# MAPLE-IR-V01.net
KiCad netlist of a schematic drawn in EAGLE
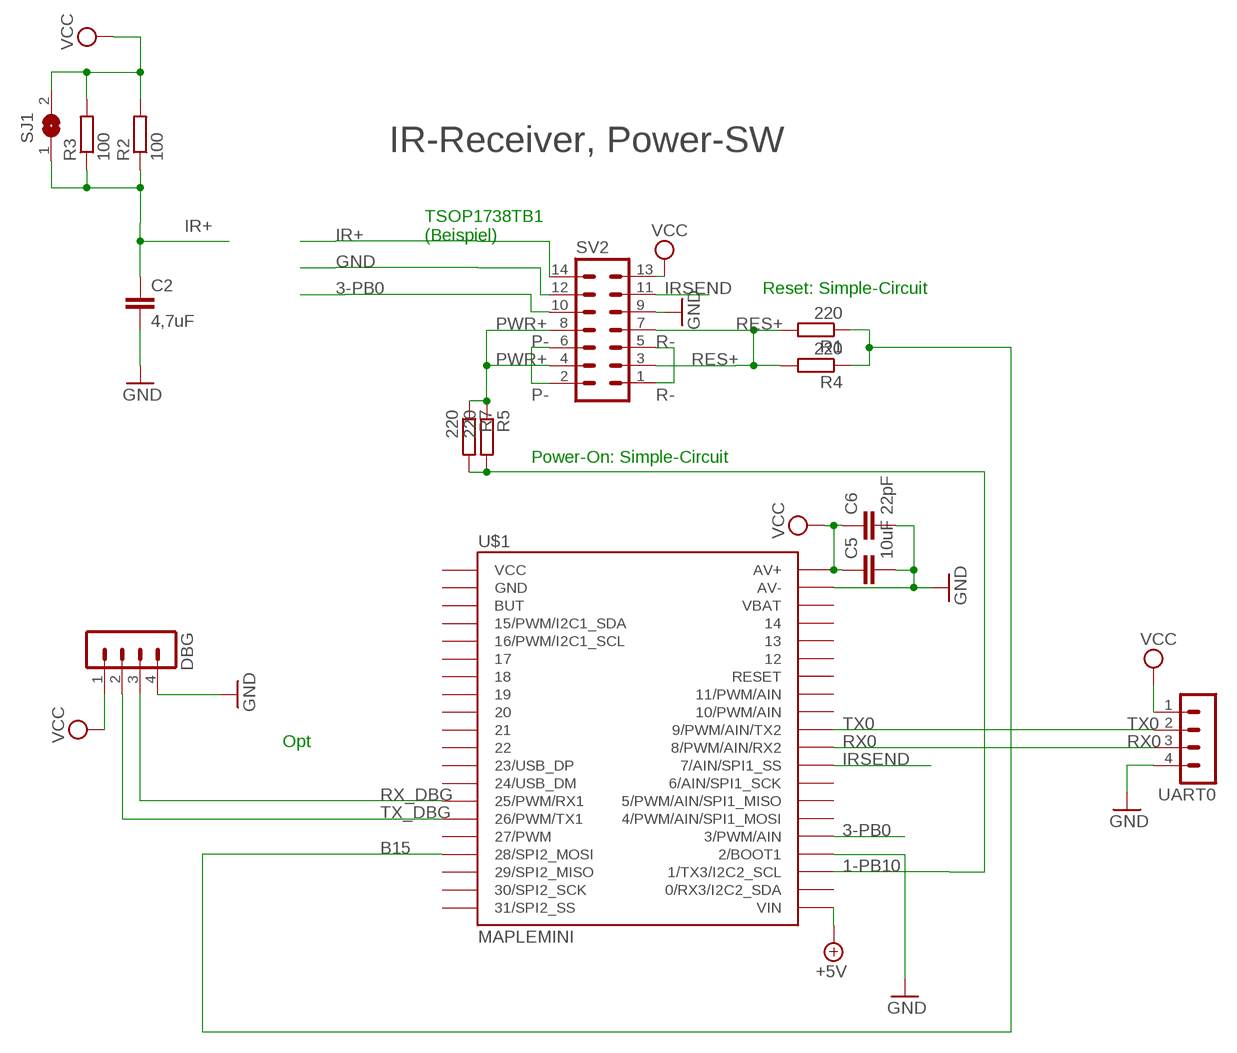
[diagram p0: schematic, sheet 1]

(export (version "E")
  (design (tool "Eeschema 10.0.6"))
  (components
    (comp (ref "C2")
      (value "4,7uF")
      (footprint "eagle-import:C1206K")
      (libsource (lib "eagle-import") (part "C-EUC1206K"))
    )
    (comp (ref "C5")
      (value "10uF")
      (footprint "eagle-import:C1210")
      (libsource (lib "eagle-import") (part "C-EUC1210"))
    )
    (comp (ref "C6")
      (value "22pF")
      (footprint "eagle-import:C0805")
      (libsource (lib "eagle-import") (part "C-EUC0805"))
    )
    (comp (ref "DBG")
      (value "MA04-1")
      (footprint "eagle-import:MA04-1")
      (libsource (lib "eagle-import") (part "MA04-1"))
    )
    (comp (ref "R1")
      (value "220")
      (footprint "eagle-import:0204_7")
      (libsource (lib "eagle-import") (part "R-EU_0204/7"))
    )
    (comp (ref "R2")
      (value "100")
      (footprint "eagle-import:0204_7")
      (libsource (lib "eagle-import") (part "R-EU_0204/7"))
    )
    (comp (ref "R3")
      (value "100")
      (footprint "eagle-import:R0805W")
      (libsource (lib "eagle-import") (part "R-EU_R0805W"))
    )
    (comp (ref "R4")
      (value "220")
      (footprint "eagle-import:R0805W")
      (libsource (lib "eagle-import") (part "R-EU_R0805W"))
    )
    (comp (ref "R5")
      (value "220")
      (footprint "eagle-import:0204_7")
      (libsource (lib "eagle-import") (part "R-EU_0204/7"))
    )
    (comp (ref "R7")
      (value "220")
      (footprint "eagle-import:R0805W")
      (libsource (lib "eagle-import") (part "R-EU_R0805W"))
    )
    (comp (ref "SJ1") (value "SJ") (footprint "eagle-import:SJ") (libsource (lib "eagle-import") (part "SJ")))
    (comp (ref "SV2")
      (value "MA07-2")
      (footprint "eagle-import:MA07-2")
      (libsource (lib "eagle-import") (part "MA07-2"))
    )
    (comp (ref "U$1")
      (value "MAPLEMINI")
      (footprint "eagle-import:20-DIP")
      (libsource (lib "eagle-import") (part "MAPLEMINI"))
    )
    (comp (ref "UART0")
      (value "MA04-1")
      (footprint "eagle-import:MA04-1")
      (libsource (lib "eagle-import") (part "MA04-1"))
    )
  )
  (nets
    (net (code "1") (name "+5V") (class "Default")
      (node (ref "U$1") (pin "21") (pinfunction "VIN_21") (pintype "bidirectional"))
    )
    (net (code "2") (name "/1-PB10") (class "Default")
      (node (ref "R5") (pin "2") (pinfunction "2_2") (pintype "passive"))
      (node (ref "R7") (pin "2") (pinfunction "2_2") (pintype "passive"))
      (node (ref "U$1") (pin "23") (pinfunction "1/TX3/I2C2_SCL_23") (pintype "bidirectional"))
    )
    (net (code "3") (name "/3-PB0") (class "Default")
      (node (ref "SV2") (pin "10") (pinfunction "10_10") (pintype "passive"))
      (node (ref "U$1") (pin "25") (pinfunction "3/PWM/AIN_25") (pintype "bidirectional"))
    )
    (net (code "4") (name "/B15") (class "Default")
      (node (ref "R1") (pin "1") (pinfunction "1_1") (pintype "passive"))
      (node (ref "R4") (pin "1") (pinfunction "1_1") (pintype "passive"))
      (node (ref "U$1") (pin "17") (pinfunction "28/SPI2_MOSI_17") (pintype "bidirectional"))
    )
    (net (code "5") (name "/IR+") (class "Default")
      (node (ref "C2") (pin "1") (pinfunction "1_1") (pintype "passive"))
      (node (ref "R2") (pin "1") (pinfunction "1_1") (pintype "passive"))
      (node (ref "R3") (pin "1") (pinfunction "1_1") (pintype "passive"))
      (node (ref "SJ1") (pin "1") (pinfunction "1_1") (pintype "passive"))
      (node (ref "SV2") (pin "14") (pinfunction "14_14") (pintype "passive"))
    )
    (net (code "6") (name "/IRSEND") (class "Default")
      (node (ref "SV2") (pin "11") (pinfunction "11_11") (pintype "passive"))
      (node (ref "U$1") (pin "29") (pinfunction "7/AIN/SPI1_SS_29") (pintype "bidirectional"))
    )
    (net (code "7") (name "/P-") (class "Default")
      (node (ref "SV2") (pin "2") (pinfunction "2_2") (pintype "passive"))
      (node (ref "SV2") (pin "6") (pinfunction "6_6") (pintype "passive"))
    )
    (net (code "8") (name "/PWR+") (class "Default")
      (node (ref "R5") (pin "1") (pinfunction "1_1") (pintype "passive"))
      (node (ref "R7") (pin "1") (pinfunction "1_1") (pintype "passive"))
      (node (ref "SV2") (pin "4") (pinfunction "4_4") (pintype "passive"))
      (node (ref "SV2") (pin "8") (pinfunction "8_8") (pintype "passive"))
    )
    (net (code "9") (name "/R-") (class "Default")
      (node (ref "SV2") (pin "1") (pinfunction "1_1") (pintype "passive"))
      (node (ref "SV2") (pin "5") (pinfunction "5_5") (pintype "passive"))
    )
    (net (code "10") (name "/RES+") (class "Default")
      (node (ref "R1") (pin "2") (pinfunction "2_2") (pintype "passive"))
      (node (ref "R4") (pin "2") (pinfunction "2_2") (pintype "passive"))
      (node (ref "SV2") (pin "3") (pinfunction "3_3") (pintype "passive"))
      (node (ref "SV2") (pin "7") (pinfunction "7_7") (pintype "passive"))
    )
    (net (code "11") (name "/RX0") (class "Default")
      (node (ref "U$1") (pin "30") (pinfunction "8/PWM/AIN/RX2_30") (pintype "bidirectional"))
      (node (ref "UART0") (pin "3") (pinfunction "3_3") (pintype "passive"))
    )
    (net (code "12") (name "/RX_DBG") (class "Default")
      (node (ref "DBG") (pin "3") (pinfunction "3_3") (pintype "passive"))
      (node (ref "U$1") (pin "14") (pinfunction "25/PWM/RX1_14") (pintype "bidirectional"))
    )
    (net (code "13") (name "/TX0") (class "Default")
      (node (ref "U$1") (pin "31") (pinfunction "9/PWM/AIN/TX2_31") (pintype "bidirectional"))
      (node (ref "UART0") (pin "2") (pinfunction "2_2") (pintype "passive"))
    )
    (net (code "14") (name "/TX_DBG") (class "Default")
      (node (ref "DBG") (pin "2") (pinfunction "2_2") (pintype "passive"))
      (node (ref "U$1") (pin "15") (pinfunction "26/PWM/TX1_15") (pintype "bidirectional"))
    )
    (net (code "15") (name "GND") (class "Default")
      (node (ref "C2") (pin "2") (pinfunction "2_2") (pintype "passive"))
      (node (ref "C5") (pin "2") (pinfunction "2_2") (pintype "passive"))
      (node (ref "C6") (pin "2") (pinfunction "2_2") (pintype "passive"))
      (node (ref "DBG") (pin "4") (pinfunction "4_4") (pintype "passive"))
      (node (ref "SV2") (pin "12") (pinfunction "12_12") (pintype "passive"))
      (node (ref "SV2") (pin "9") (pinfunction "9_9") (pintype "passive"))
      (node (ref "U$1") (pin "24") (pinfunction "2/BOOT1_24") (pintype "bidirectional"))
      (node (ref "U$1") (pin "39") (pinfunction "AV-_39") (pintype "bidirectional"))
      (node (ref "UART0") (pin "4") (pinfunction "4_4") (pintype "passive"))
    )
    (net (code "16") (name "VCC") (class "Default")
      (node (ref "C5") (pin "1") (pinfunction "1_1") (pintype "passive"))
      (node (ref "C6") (pin "1") (pinfunction "1_1") (pintype "passive"))
      (node (ref "DBG") (pin "1") (pinfunction "1_1") (pintype "passive"))
      (node (ref "R2") (pin "2") (pinfunction "2_2") (pintype "passive"))
      (node (ref "R3") (pin "2") (pinfunction "2_2") (pintype "passive"))
      (node (ref "SJ1") (pin "2") (pinfunction "2_2") (pintype "passive"))
      (node (ref "SV2") (pin "13") (pinfunction "13_13") (pintype "passive"))
      (node (ref "U$1") (pin "40") (pinfunction "AV+_40") (pintype "bidirectional"))
      (node (ref "UART0") (pin "1") (pinfunction "1_1") (pintype "passive"))
    )
    (net (code "17") (name "unconnected-(U$1-0{slash}RX3{slash}I2C2_SDA-Pad22)") (class "Default")
      (node (ref "U$1") (pin "22") (pinfunction "0/RX3/I2C2_SDA_22") (pintype "bidirectional"))
    )
    (net (code "18") (name "unconnected-(U$1-4{slash}PWM{slash}AIN{slash}SPI1_MOSI-Pad26)") (class "Default")
      (node (ref "U$1") (pin "26") (pinfunction "4/PWM/AIN/SPI1_MOSI_26") (pintype "bidirectional"))
    )
    (net (code "19") (name "unconnected-(U$1-5{slash}PWM{slash}AIN{slash}SPI1_MISO-Pad27)") (class "Default")
      (node (ref "U$1") (pin "27") (pinfunction "5/PWM/AIN/SPI1_MISO_27") (pintype "bidirectional"))
    )
    (net (code "20") (name "unconnected-(U$1-6{slash}AIN{slash}SPI1_SCK-Pad28)") (class "Default")
      (node (ref "U$1") (pin "28") (pinfunction "6/AIN/SPI1_SCK_28") (pintype "bidirectional"))
    )
    (net (code "21") (name "unconnected-(U$1-10{slash}PWM{slash}AIN-Pad32)") (class "Default")
      (node (ref "U$1") (pin "32") (pinfunction "10/PWM/AIN_32") (pintype "bidirectional"))
    )
    (net (code "22") (name "unconnected-(U$1-11{slash}PWM{slash}AIN-Pad33)") (class "Default")
      (node (ref "U$1") (pin "33") (pinfunction "11/PWM/AIN_33") (pintype "bidirectional"))
    )
    (net (code "23") (name "unconnected-(U$1-12-Pad35)") (class "Default")
      (node (ref "U$1") (pin "35") (pinfunction "12_35") (pintype "bidirectional"))
    )
    (net (code "24") (name "unconnected-(U$1-13-Pad36)") (class "Default")
      (node (ref "U$1") (pin "36") (pinfunction "13_36") (pintype "bidirectional"))
    )
    (net (code "25") (name "unconnected-(U$1-14-Pad37)") (class "Default")
      (node (ref "U$1") (pin "37") (pinfunction "14_37") (pintype "bidirectional"))
    )
    (net (code "26") (name "unconnected-(U$1-15{slash}PWM{slash}I2C1_SDA-Pad4)") (class "Default")
      (node (ref "U$1") (pin "4") (pinfunction "15/PWM/I2C1_SDA_4") (pintype "bidirectional"))
    )
    (net (code "27") (name "unconnected-(U$1-16{slash}PWM{slash}I2C1_SCL-Pad5)") (class "Default")
      (node (ref "U$1") (pin "5") (pinfunction "16/PWM/I2C1_SCL_5") (pintype "bidirectional"))
    )
    (net (code "28") (name "unconnected-(U$1-17-Pad6)") (class "Default")
      (node (ref "U$1") (pin "6") (pinfunction "17_6") (pintype "bidirectional"))
    )
    (net (code "29") (name "unconnected-(U$1-18-Pad7)") (class "Default")
      (node (ref "U$1") (pin "7") (pinfunction "18_7") (pintype "bidirectional"))
    )
    (net (code "30") (name "unconnected-(U$1-19-Pad8)") (class "Default")
      (node (ref "U$1") (pin "8") (pinfunction "19_8") (pintype "bidirectional"))
    )
    (net (code "31") (name "unconnected-(U$1-20-Pad9)") (class "Default")
      (node (ref "U$1") (pin "9") (pinfunction "20_9") (pintype "bidirectional"))
    )
    (net (code "32") (name "unconnected-(U$1-21-Pad10)") (class "Default")
      (node (ref "U$1") (pin "10") (pinfunction "21_10") (pintype "bidirectional"))
    )
    (net (code "33") (name "unconnected-(U$1-22-Pad11)") (class "Default")
      (node (ref "U$1") (pin "11") (pinfunction "22_11") (pintype "bidirectional"))
    )
    (net (code "34") (name "unconnected-(U$1-23{slash}USB_DP-Pad12)") (class "Default")
      (node (ref "U$1") (pin "12") (pinfunction "23/USB_DP_12") (pintype "bidirectional"))
    )
    (net (code "35") (name "unconnected-(U$1-24{slash}USB_DM-Pad13)") (class "Default")
      (node (ref "U$1") (pin "13") (pinfunction "24/USB_DM_13") (pintype "bidirectional"))
    )
    (net (code "36") (name "unconnected-(U$1-27{slash}PWM-Pad16)") (class "Default")
      (node (ref "U$1") (pin "16") (pinfunction "27/PWM_16") (pintype "bidirectional"))
    )
    (net (code "37") (name "unconnected-(U$1-29{slash}SPI2_MISO-Pad18)") (class "Default")
      (node (ref "U$1") (pin "18") (pinfunction "29/SPI2_MISO_18") (pintype "bidirectional"))
    )
    (net (code "38") (name "unconnected-(U$1-30{slash}SPI2_SCK-Pad19)") (class "Default")
      (node (ref "U$1") (pin "19") (pinfunction "30/SPI2_SCK_19") (pintype "bidirectional"))
    )
    (net (code "39") (name "unconnected-(U$1-31{slash}SPI2_SS-Pad20)") (class "Default")
      (node (ref "U$1") (pin "20") (pinfunction "31/SPI2_SS_20") (pintype "bidirectional"))
    )
    (net (code "40") (name "unconnected-(U$1-BUT-Pad3)") (class "Default")
      (node (ref "U$1") (pin "3") (pinfunction "BUT_3") (pintype "bidirectional"))
    )
    (net (code "41") (name "unconnected-(U$1-GND-Pad2)") (class "Default")
      (node (ref "U$1") (pin "2") (pinfunction "GND_2") (pintype "bidirectional"))
    )
    (net (code "42") (name "unconnected-(U$1-RESET-Pad34)") (class "Default")
      (node (ref "U$1") (pin "34") (pinfunction "RESET_34") (pintype "bidirectional"))
    )
    (net (code "43") (name "unconnected-(U$1-VBAT-Pad38)") (class "Default")
      (node (ref "U$1") (pin "38") (pinfunction "VBAT_38") (pintype "bidirectional"))
    )
    (net (code "44") (name "unconnected-(U$1-VCC-Pad1)") (class "Default")
      (node (ref "U$1") (pin "1") (pinfunction "VCC_1") (pintype "bidirectional"))
    )
  )
)
